# LKS_074DO_0406.net
KiCad netlist of a schematic drawn in Altium Designer
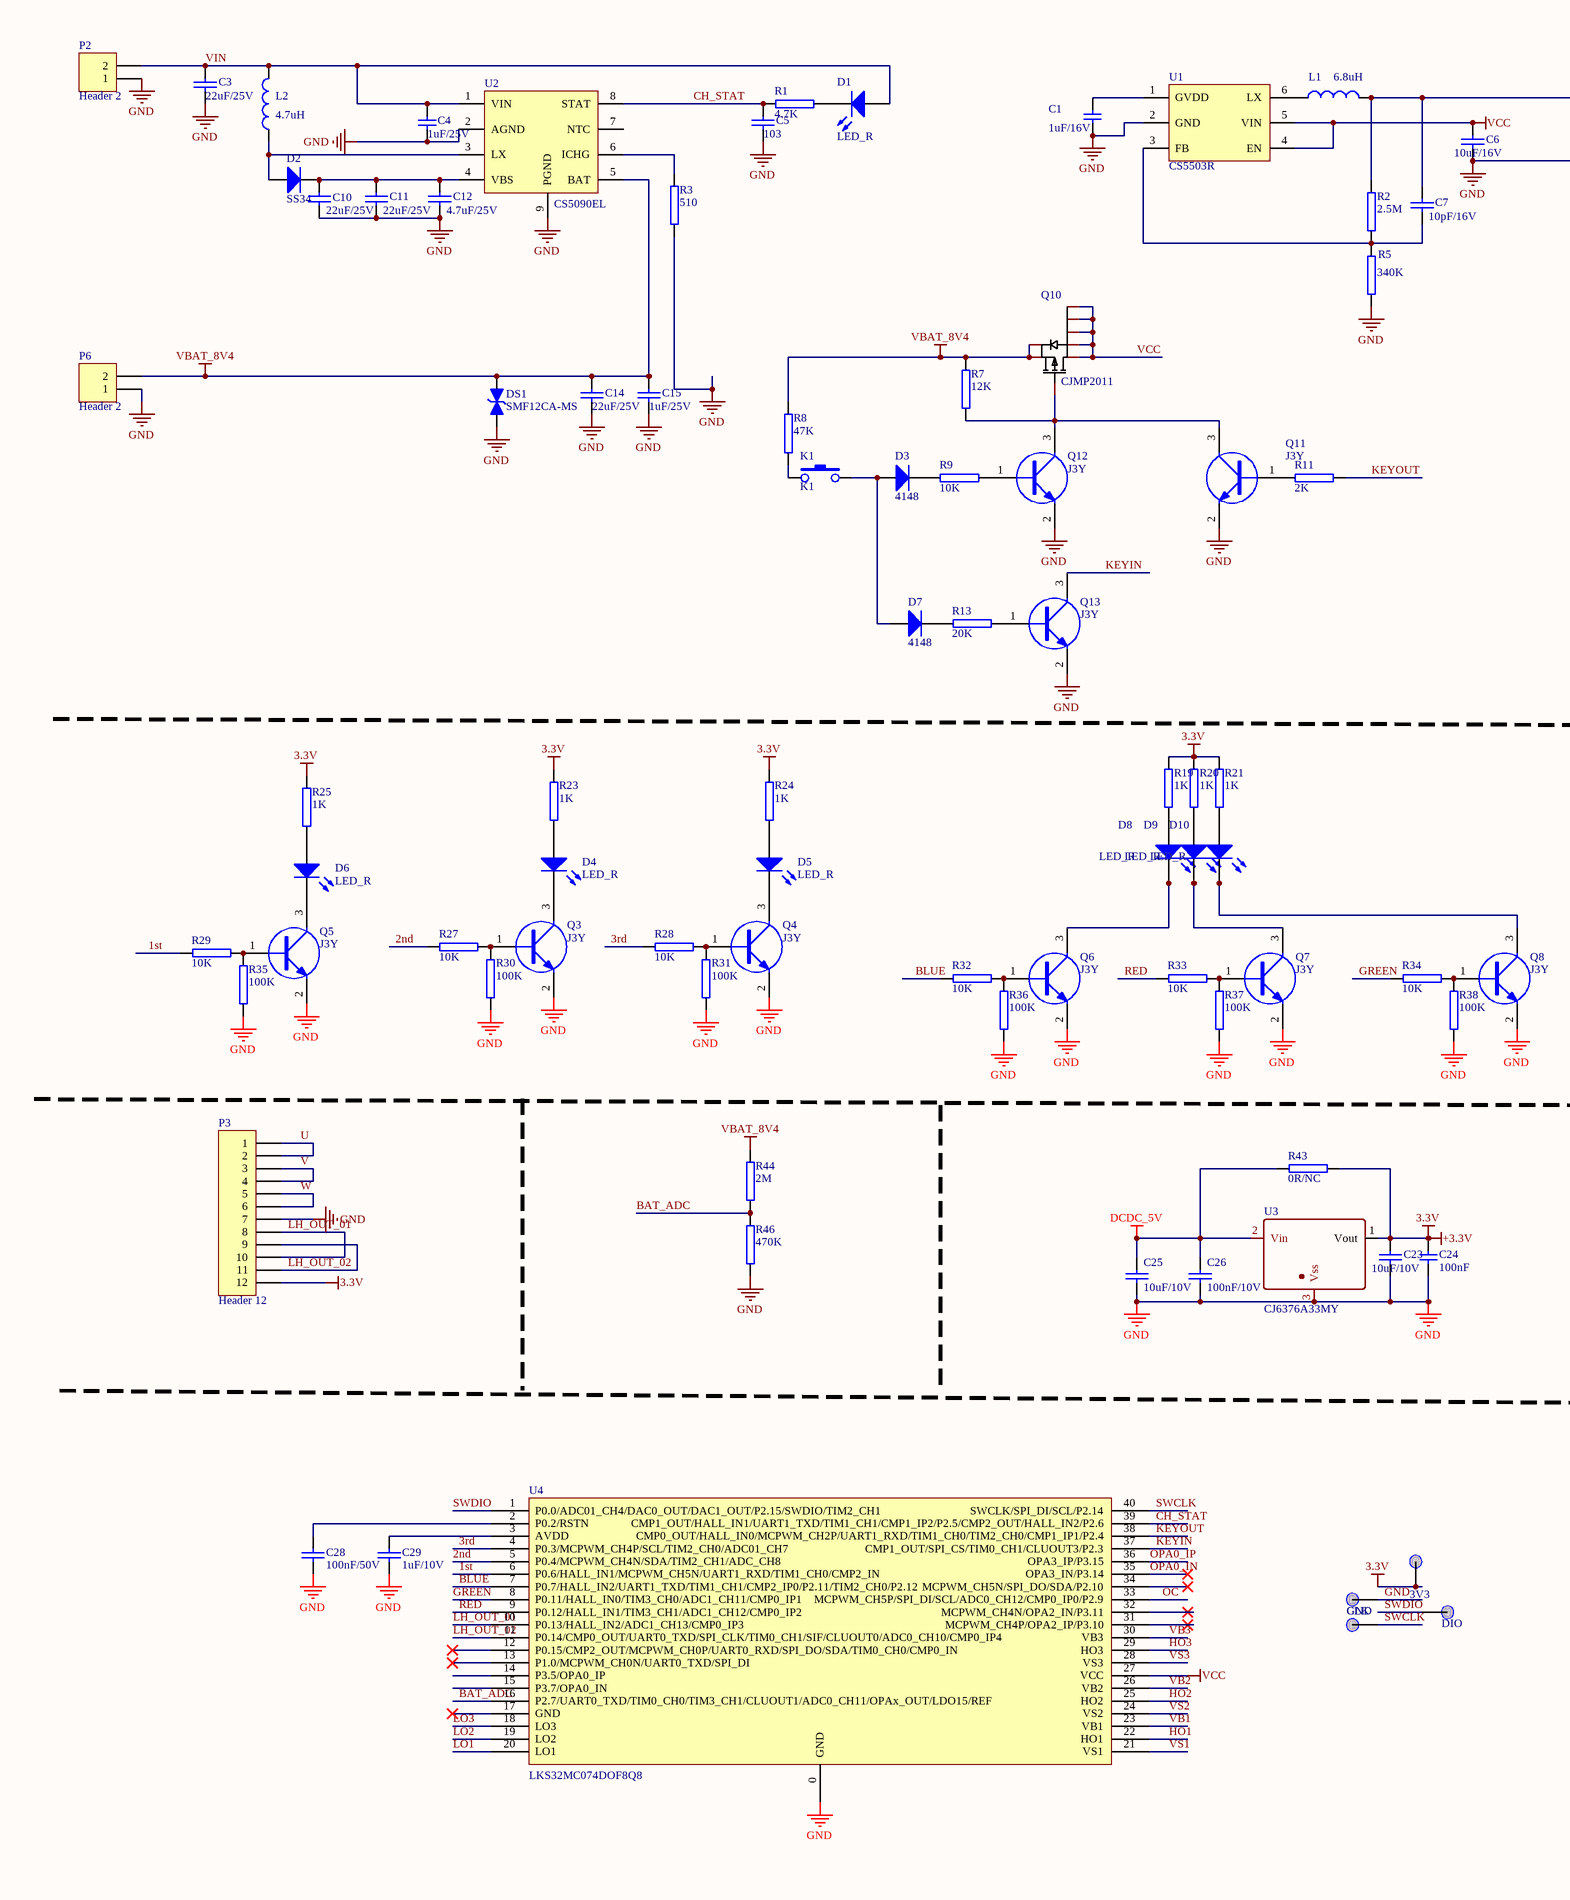
[diagram p0: LKS_074DO_0406.SchDoc, left]
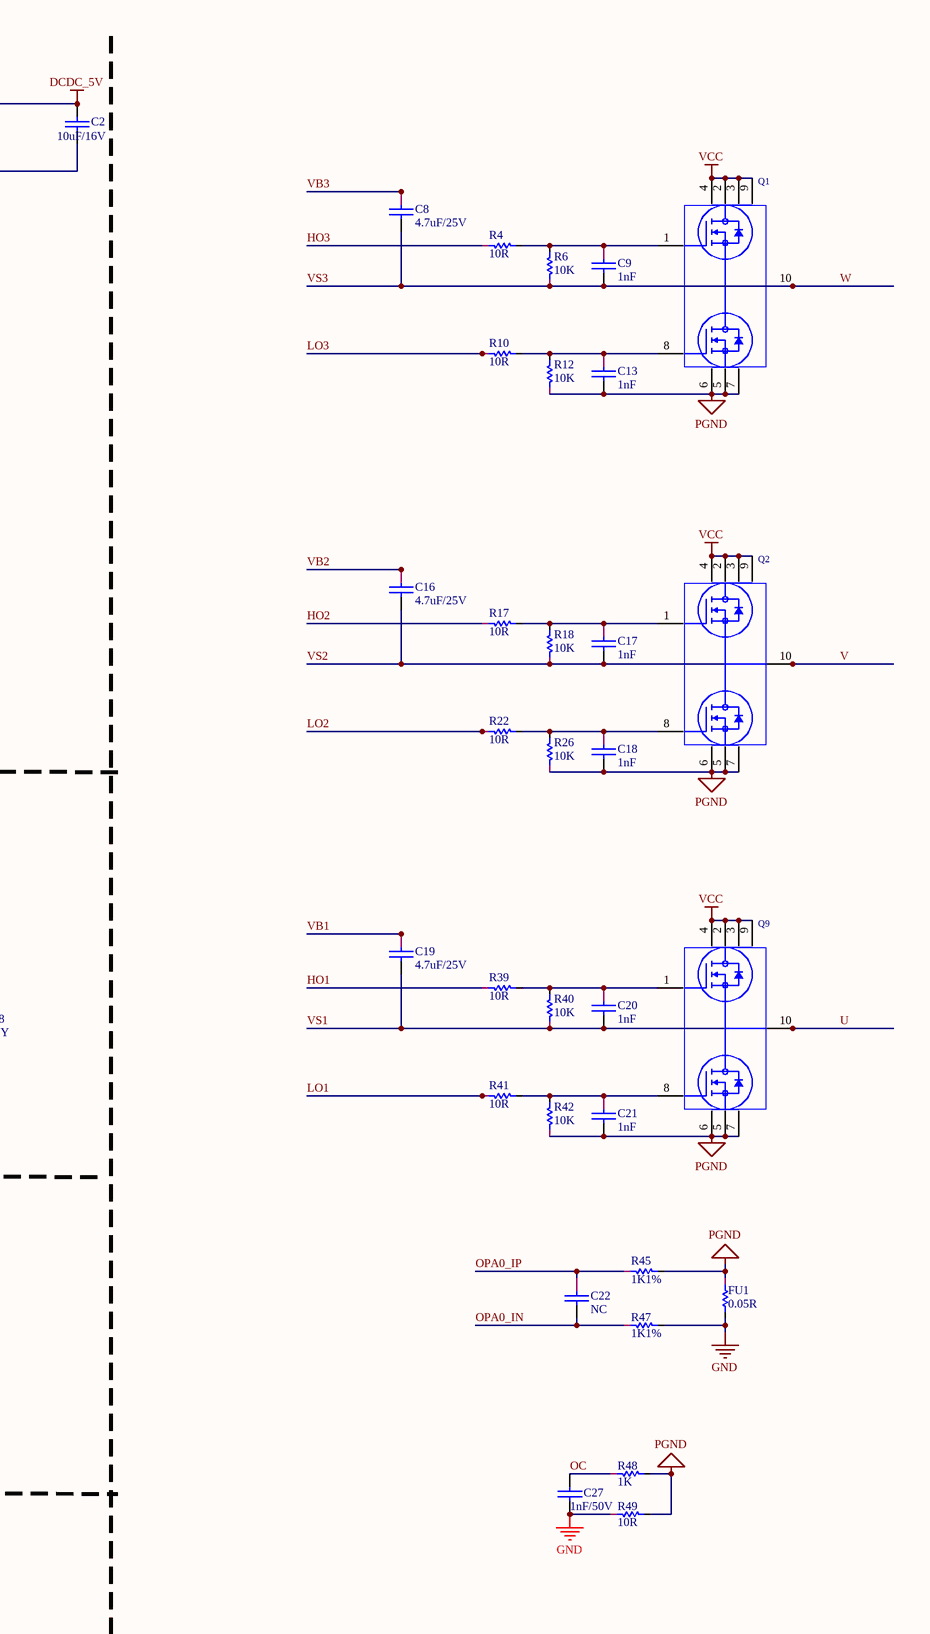
[diagram p1: LKS_074DO_0406.SchDoc, right]

(export (version "E")
  (design (tool "Eeschema 10.0.6"))
  (components
    (comp (ref "3V3") (value "test") (footprint "piot") (libsource (lib "LKS074DO_BRUSH_0329") (part "test")))
    (comp (ref "C1") (value "1uF/16V") (footprint "C 0402_M") (libsource (lib "") (part "CAP_2")))
    (comp (ref "C2")
      (value "10uF/16V")
      (footprint "C 0603_M")
      (description "Capacitor")
      (libsource (lib "") (part "CAP_1"))
    )
    (comp (ref "C3")
      (value "22uF/25V")
      (footprint "C 0603_M")
      (description "Capacitor")
      (libsource (lib "") (part "CAP_1"))
    )
    (comp (ref "C4") (value "1uF/25V") (footprint "C 0402_M") (libsource (lib "") (part "CAP_2")))
    (comp (ref "C5")
      (value "103")
      (footprint "R 0402_M")
      (description "Capacitor")
      (libsource (lib "") (part "CAP_1"))
    )
    (comp (ref "C6")
      (value "10uF/16V")
      (footprint "C 0603_M")
      (description "Capacitor")
      (libsource (lib "") (part "CAP_1"))
    )
    (comp (ref "C7")
      (value "10pF/16V")
      (footprint "C 0402_M")
      (description "Capacitor")
      (libsource (lib "") (part "CAP_1"))
    )
    (comp (ref "C8")
      (value "4.7uF/25V")
      (footprint "C 0402_M")
      (description "Capacitor")
      (libsource (lib "*") (part "CAP"))
    )
    (comp (ref "C9")
      (value "1nF")
      (footprint "C 0402_M")
      (description "Capacitor")
      (libsource (lib "*") (part "CAP"))
    )
    (comp (ref "C10")
      (value "22uF/25V")
      (footprint "C 0603_M")
      (description "Capacitor")
      (libsource (lib "") (part "CAP_1"))
    )
    (comp (ref "C11")
      (value "22uF/25V")
      (footprint "C 0603_M")
      (description "Capacitor")
      (libsource (lib "") (part "CAP_1"))
    )
    (comp (ref "C12")
      (value "4.7uF/25V")
      (footprint "C 0402_M")
      (description "Capacitor")
      (libsource (lib "") (part "CAP_1"))
    )
    (comp (ref "C13")
      (value "1nF")
      (footprint "C 0402_M")
      (description "Capacitor")
      (libsource (lib "*") (part "CAP"))
    )
    (comp (ref "C14")
      (value "22uF/25V")
      (footprint "C 0603_M")
      (description "Capacitor")
      (libsource (lib "") (part "CAP_1"))
    )
    (comp (ref "C15")
      (value "1uF/25V")
      (footprint "C 0402_M")
      (description "Capacitor")
      (libsource (lib "") (part "CAP_1"))
    )
    (comp (ref "C16")
      (value "4.7uF/25V")
      (footprint "C 0402_M")
      (description "Capacitor")
      (libsource (lib "*") (part "CAP"))
    )
    (comp (ref "C17")
      (value "1nF")
      (footprint "C 0402_M")
      (description "Capacitor")
      (libsource (lib "*") (part "CAP"))
    )
    (comp (ref "C18")
      (value "1nF")
      (footprint "C 0402_M")
      (description "Capacitor")
      (libsource (lib "*") (part "CAP"))
    )
    (comp (ref "C19")
      (value "4.7uF/25V")
      (footprint "C 0402_M")
      (description "Capacitor")
      (libsource (lib "*") (part "CAP"))
    )
    (comp (ref "C20")
      (value "1nF")
      (footprint "C 0402_M")
      (description "Capacitor")
      (libsource (lib "*") (part "CAP"))
    )
    (comp (ref "C21")
      (value "1nF")
      (footprint "C 0402_M")
      (description "Capacitor")
      (libsource (lib "*") (part "CAP"))
    )
    (comp (ref "C22")
      (value "NC")
      (footprint "C 0402_M")
      (description "Capacitor")
      (libsource (lib "*") (part "CAP"))
    )
    (comp (ref "C23")
      (value "10uF/10V")
      (footprint "C 0603_M")
      (description "Capacitor")
      (libsource (lib "") (part "CAP_1"))
    )
    (comp (ref "C24") (value "100nF") (footprint "C 0402_M") (libsource (lib "") (part "CAP_2")))
    (comp (ref "C25")
      (value "10uF/10V")
      (footprint "C 0603_M")
      (description "Capacitor")
      (libsource (lib "") (part "CAP_1"))
    )
    (comp (ref "C26")
      (value "100nF/10V")
      (footprint "C 0402_M")
      (description "Capacitor")
      (libsource (lib "") (part "CAP_1"))
    )
    (comp (ref "C27")
      (value "1nF/50V")
      (footprint "C 0402_M")
      (description "Capacitor")
      (libsource (lib "*") (part "C"))
    )
    (comp (ref "C28")
      (value "100nF/50V")
      (footprint "C 0402_M")
      (description "Capacitor")
      (libsource (lib "*") (part "C"))
    )
    (comp (ref "C29")
      (value "1uF/10V")
      (footprint "C 0402_M")
      (description "Capacitor")
      (libsource (lib "*") (part "C"))
    )
    (comp (ref "CLK") (value "test") (footprint "piot") (libsource (lib "LKS074DO_BRUSH_0329") (part "test")))
    (comp (ref "D1") (value "LED_R") (footprint "0603-LED") (libsource (lib "PuXun1") (part "LED")))
    (comp (ref "D2")
      (value "SS34")
      (footprint "SOD123FL")
      (description "Default Diode")
      (fields (field (name "PUBLISHER") "Altium Limited"))
      (libsource (lib "LKS034DO_Motor_0520_1") (part "Diode"))
    )
    (comp (ref "D3")
      (value "4148")
      (footprint "SOD-323")
      (description "Default Diode")
      (fields (field (name "PUBLISHER") "Altium Limited"))
      (libsource (lib "LKS034DO_Motor_0520_1") (part "Diode"))
    )
    (comp (ref "D4") (value "LED_R") (footprint "0603-LED") (libsource (lib "PuXun1") (part "LED")))
    (comp (ref "D5") (value "LED_R") (footprint "0603-LED") (libsource (lib "PuXun1") (part "LED")))
    (comp (ref "D6") (value "LED_R") (footprint "0603-LED") (libsource (lib "PuXun1") (part "LED")))
    (comp (ref "D7")
      (value "4148")
      (footprint "SOD-323")
      (description "Default Diode")
      (fields (field (name "PUBLISHER") "Altium Limited"))
      (libsource (lib "LKS034DO_Motor_0520_1") (part "Diode"))
    )
    (comp (ref "D8") (value "LED_R") (footprint "0603-LED") (libsource (lib "PuXun1") (part "LED")))
    (comp (ref "D9") (value "LED_R") (footprint "0603-LED") (libsource (lib "PuXun1") (part "LED")))
    (comp (ref "D10") (value "LED_R") (footprint "0603-LED") (libsource (lib "PuXun1") (part "LED")))
    (comp (ref "DIO") (value "test") (footprint "piot") (libsource (lib "LKS074DO_BRUSH_0329") (part "test")))
    (comp (ref "DS1")
      (value "SMF12CA-MS")
      (footprint "SOD-123F")
      (description "12V/19.9V")
      (libsource (lib "*") (part "DIODE-3"))
    )
    (comp (ref "FU1") (value "0.05R") (footprint "R 0805_M") (libsource (lib "*") (part "RAS")))
    (comp (ref "GND") (value "test") (footprint "piot") (libsource (lib "LKS074DO_BRUSH_0329") (part "test")))
    (comp (ref "K1") (value "K1") (footprint "SMD3.3X3.3X2") (libsource (lib "SCHLIB_NEW") (part "K1")))
    (comp (ref "L1")
      (value "6.8uH")
      (footprint "SMD3.5X3 .2- duplicate")
      (description "Inductor")
      (fields (field (name "PUBLISHER") "Altium Limited"))
      (libsource (lib "Miscellaneous Devices") (part "Inductor"))
    )
    (comp (ref "L2")
      (value "4.7uH")
      (footprint "SMD3.5X3 .2- duplicate")
      (description "Inductor")
      (fields (field (name "PUBLISHER") "Altium Limited"))
      (libsource (lib "Miscellaneous Devices") (part "Inductor"))
    )
    (comp (ref "P2")
      (value "Header 2")
      (footprint "CONN_SMD_2P_0.6")
      (description "Header, 2-Pin")
      (fields (field (name "PUBLISHER") "Altium Limited"))
      (libsource (lib "Miscellaneous Connectors") (part "Header 2"))
    )
    (comp (ref "P3")
      (value "Header 12")
      (footprint "SMD-12")
      (description "Header, 12-Pin")
      (fields (field (name "PUBLISHER") "Altium Limited"))
      (libsource (lib "Miscellaneous Connectors") (part "Header 12"))
    )
    (comp (ref "P6")
      (value "Header 2")
      (footprint "CONN_SMD_2P_0.6")
      (description "Header, 2-Pin")
      (fields (field (name "PUBLISHER") "Altium Limited"))
      (libsource (lib "Miscellaneous Connectors") (part "Header 2"))
    )
    (comp (ref "Q1") (value "CJBM3020") (footprint "DFN-3X3_8") (libsource (lib "*") (part "CJBM3020")))
    (comp (ref "Q2") (value "CJBM3020") (footprint "DFN-3X3_8") (libsource (lib "*") (part "CJBM3020")))
    (comp (ref "Q3")
      (value "J3Y")
      (footprint "SOT-23")
      (description "NPN Transistor")
      (libsource (lib "*") (part "NPN"))
    )
    (comp (ref "Q4")
      (value "J3Y")
      (footprint "SOT-23")
      (description "NPN Transistor")
      (libsource (lib "*") (part "NPN"))
    )
    (comp (ref "Q5")
      (value "J3Y")
      (footprint "SOT-23")
      (description "NPN Transistor")
      (libsource (lib "*") (part "NPN"))
    )
    (comp (ref "Q6")
      (value "J3Y")
      (footprint "SOT-23")
      (description "NPN Transistor")
      (libsource (lib "*") (part "NPN"))
    )
    (comp (ref "Q7")
      (value "J3Y")
      (footprint "SOT-23")
      (description "NPN Transistor")
      (libsource (lib "*") (part "NPN"))
    )
    (comp (ref "Q8")
      (value "J3Y")
      (footprint "SOT-23")
      (description "NPN Transistor")
      (libsource (lib "*") (part "NPN"))
    )
    (comp (ref "Q9") (value "CJBM3020") (footprint "DFN-3X3_8") (libsource (lib "*") (part "CJBM3020")))
    (comp (ref "Q10")
      (value "CJMP2011")
      (footprint "DFN-6-2X2")
      (libsource (lib "LKS074DO_BRUSH_0329") (part "CJMP2011"))
    )
    (comp (ref "Q11")
      (value "J3Y")
      (footprint "SOT-23")
      (description "NPN Transistor")
      (libsource (lib "*") (part "NPN"))
    )
    (comp (ref "Q12")
      (value "J3Y")
      (footprint "SOT-23")
      (description "NPN Transistor")
      (libsource (lib "*") (part "NPN"))
    )
    (comp (ref "Q13")
      (value "J3Y")
      (footprint "SOT-23")
      (description "NPN Transistor")
      (libsource (lib "*") (part "NPN"))
    )
    (comp (ref "R1") (value "4.7K") (footprint "C 0402_M") (libsource (lib "*") (part "RES2_S")))
    (comp (ref "R2") (value "2.5M") (footprint "C 0402_M") (libsource (lib "*") (part "RES2_S")))
    (comp (ref "R3") (value "510") (footprint "R 0402_M") (libsource (lib "*") (part "RES2_S")))
    (comp (ref "R4") (value "10R") (footprint "R 0402_M") (libsource (lib "*") (part "RAS")))
    (comp (ref "R5") (value "340K") (footprint "C 0402_M") (libsource (lib "*") (part "RES2_S")))
    (comp (ref "R6") (value "10K") (footprint "R 0402_M") (libsource (lib "*") (part "RAS")))
    (comp (ref "R7") (value "12K") (footprint "C 0402_M") (libsource (lib "*") (part "RES2_S")))
    (comp (ref "R8") (value "47K") (footprint "C 0402_M") (libsource (lib "*") (part "RES2_S")))
    (comp (ref "R9") (value "10K") (footprint "C 0402_M") (libsource (lib "*") (part "RES2_S")))
    (comp (ref "R10") (value "10R") (footprint "R 0402_M") (libsource (lib "*") (part "RAS")))
    (comp (ref "R11") (value "2K") (footprint "C 0402_M") (libsource (lib "*") (part "RES2_S")))
    (comp (ref "R12") (value "10K") (footprint "R 0402_M") (libsource (lib "*") (part "RAS")))
    (comp (ref "R13") (value "20K") (footprint "C 0402_M") (libsource (lib "*") (part "RES2_S")))
    (comp (ref "R17") (value "10R") (footprint "R 0402_M") (libsource (lib "*") (part "RAS")))
    (comp (ref "R18") (value "10K") (footprint "R 0402_M") (libsource (lib "*") (part "RAS")))
    (comp (ref "R19") (value "1K") (footprint "C 0402_M") (libsource (lib "*") (part "RES2_S")))
    (comp (ref "R20") (value "1K") (footprint "C 0402_M") (libsource (lib "*") (part "RES2_S")))
    (comp (ref "R21") (value "1K") (footprint "C 0402_M") (libsource (lib "*") (part "RES2_S")))
    (comp (ref "R22") (value "10R") (footprint "R 0402_M") (libsource (lib "*") (part "RAS")))
    (comp (ref "R23") (value "1K") (footprint "C 0402_M") (libsource (lib "*") (part "RES2_S")))
    (comp (ref "R24") (value "1K") (footprint "C 0402_M") (libsource (lib "*") (part "RES2_S")))
    (comp (ref "R25") (value "1K") (footprint "C 0402_M") (libsource (lib "*") (part "RES2_S")))
    (comp (ref "R26") (value "10K") (footprint "R 0402_M") (libsource (lib "*") (part "RAS")))
    (comp (ref "R27") (value "10K") (footprint "C 0402_M") (libsource (lib "*") (part "RES2_S")))
    (comp (ref "R28") (value "10K") (footprint "C 0402_M") (libsource (lib "*") (part "RES2_S")))
    (comp (ref "R29") (value "10K") (footprint "C 0402_M") (libsource (lib "*") (part "RES2_S")))
    (comp (ref "R30") (value "100K") (footprint "C 0402_M") (libsource (lib "*") (part "RES2_S")))
    (comp (ref "R31") (value "100K") (footprint "C 0402_M") (libsource (lib "*") (part "RES2_S")))
    (comp (ref "R32") (value "10K") (footprint "C 0402_M") (libsource (lib "*") (part "RES2_S")))
    (comp (ref "R33") (value "10K") (footprint "C 0402_M") (libsource (lib "*") (part "RES2_S")))
    (comp (ref "R34") (value "10K") (footprint "C 0402_M") (libsource (lib "*") (part "RES2_S")))
    (comp (ref "R35") (value "100K") (footprint "C 0402_M") (libsource (lib "*") (part "RES2_S")))
    (comp (ref "R36") (value "100K") (footprint "C 0402_M") (libsource (lib "*") (part "RES2_S")))
    (comp (ref "R37") (value "100K") (footprint "C 0402_M") (libsource (lib "*") (part "RES2_S")))
    (comp (ref "R38") (value "100K") (footprint "C 0402_M") (libsource (lib "*") (part "RES2_S")))
    (comp (ref "R39") (value "10R") (footprint "R 0402_M") (libsource (lib "*") (part "RAS")))
    (comp (ref "R40") (value "10K") (footprint "R 0402_M") (libsource (lib "*") (part "RAS")))
    (comp (ref "R41") (value "10R") (footprint "R 0402_M") (libsource (lib "*") (part "RAS")))
    (comp (ref "R42") (value "10K") (footprint "R 0402_M") (libsource (lib "*") (part "RAS")))
    (comp (ref "R43") (value "0R/NC") (footprint "0603") (libsource (lib "*") (part "RES2_S")))
    (comp (ref "R44") (value "2M") (footprint "C 0402_M") (libsource (lib "*") (part "RES2_S")))
    (comp (ref "R45") (value "1K1%") (footprint "R 0402_M") (libsource (lib "*") (part "RAS")))
    (comp (ref "R46") (value "470K") (footprint "C 0402_M") (libsource (lib "*") (part "RES2_S")))
    (comp (ref "R47") (value "1K1%") (footprint "R 0402_M") (libsource (lib "*") (part "RAS")))
    (comp (ref "R48") (value "1K") (footprint "R 0402_M") (libsource (lib "*") (part "RAS")))
    (comp (ref "R49") (value "10R") (footprint "R 0402_M") (libsource (lib "*") (part "RAS")))
    (comp (ref "U1")
      (value "CS5503R")
      (footprint "SOT23-6L")
      (libsource (lib "LKS034DO_Motor_0520_1") (part "CS5503R"))
    )
    (comp (ref "U2")
      (value "CS5090EL")
      (footprint "DFN2X2_8_0.5")
      (libsource (lib "LKS034DO_Motor_0520_1") (part "CS5090EL"))
    )
    (comp (ref "U3")
      (value "CJ6376A33MY")
      (footprint "SOT-23")
      (libsource (lib "LKS034DO_Motor_0520_1") (part "78L15"))
    )
    (comp (ref "U4")
      (value "LKS32MC074DOF8Q8")
      (footprint "QFN40")
      (description "芯片")
      (libsource (lib "Q_LINKO_V1.0") (part "LKS32MC074DF8Q8"))
    )
  )
  (nets
    (net (code "1") (name "+3.3V") (class "Default")
      (node (ref "3V3") (pin "1") (pinfunction "1_1") (pintype "passive"))
      (node (ref "C23") (pin "2") (pinfunction "2_2") (pintype "passive"))
      (node (ref "C24") (pin "1") (pinfunction "1_1") (pintype "passive"))
      (node (ref "P3") (pin "12") (pinfunction "12_12") (pintype "passive"))
      (node (ref "R19") (pin "2") (pinfunction "2_2") (pintype "passive"))
      (node (ref "R20") (pin "2") (pinfunction "2_2") (pintype "passive"))
      (node (ref "R21") (pin "2") (pinfunction "2_2") (pintype "passive"))
      (node (ref "R23") (pin "2") (pinfunction "2_2") (pintype "passive"))
      (node (ref "R24") (pin "2") (pinfunction "2_2") (pintype "passive"))
      (node (ref "R25") (pin "2") (pinfunction "2_2") (pintype "passive"))
      (node (ref "R43") (pin "2") (pinfunction "2_2") (pintype "passive"))
      (node (ref "U3") (pin "1") (pinfunction "Vout_1") (pintype "passive"))
    )
    (net (code "2") (name "/1st") (class "Default")
      (node (ref "R29") (pin "2") (pinfunction "2_2") (pintype "passive"))
      (node (ref "U4") (pin "6") (pinfunction "P0.6/HALL_IN1/MCPWM_CH5N/UART1_RXD/TIM1_CH0/CMP2_IN_6") (pintype "passive"))
    )
    (net (code "3") (name "/2nd") (class "Default")
      (node (ref "R27") (pin "2") (pinfunction "2_2") (pintype "passive"))
      (node (ref "U4") (pin "5") (pinfunction "P0.4/MCPWM_CH4N/SDA/TIM2_CH1/ADC_CH8_5") (pintype "passive"))
    )
    (net (code "4") (name "/3rd") (class "Default")
      (node (ref "R28") (pin "2") (pinfunction "2_2") (pintype "passive"))
      (node (ref "U4") (pin "4") (pinfunction "P0.3/MCPWM_CH4P/SCL/TIM2_CH0/ADC01_CH7_4") (pintype "passive"))
    )
    (net (code "5") (name "/BAT_ADC") (class "Default")
      (node (ref "R44") (pin "2") (pinfunction "2_2") (pintype "passive"))
      (node (ref "R46") (pin "1") (pinfunction "1_1") (pintype "passive"))
      (node (ref "U4") (pin "16") (pinfunction "P2.7/UART0_TXD/TIM0_CH0/TIM3_CH1/CLUOUT1/ADC0_CH11/OPAx_OUT/LDO15/REF_16") (pintype "passive"))
    )
    (net (code "6") (name "/BLUE") (class "Default")
      (node (ref "R32") (pin "2") (pinfunction "2_2") (pintype "passive"))
      (node (ref "U4") (pin "7") (pinfunction "P0.7/HALL_IN2/UART1_TXD/TIM1_CH1/CMP2_IP0/P2.11/TIM2_CH0/P2.12_7") (pintype "passive"))
    )
    (net (code "7") (name "/CH_STAT") (class "Default")
      (node (ref "C5") (pin "2") (pinfunction "2_2") (pintype "passive"))
      (node (ref "R1") (pin "1") (pinfunction "1_1") (pintype "passive"))
      (node (ref "U2") (pin "8") (pinfunction "STAT_8") (pintype "passive"))
      (node (ref "U4") (pin "39") (pinfunction "CMP1_OUT/HALL_IN1/UART1_TXD/TIM1_CH1/CMP1_IP2/P2.5/CMP2_OUT/HALL_IN2/P2.6_39") (pintype "passive"))
    )
    (net (code "8") (name "/GREEN") (class "Default")
      (node (ref "R34") (pin "2") (pinfunction "2_2") (pintype "passive"))
      (node (ref "U4") (pin "8") (pinfunction "P0.11/HALL_IN0/TIM3_CH0/ADC1_CH11/CMP0_IP1_8") (pintype "passive"))
    )
    (net (code "9") (name "/HO1") (class "Default")
      (node (ref "R39") (pin "2") (pinfunction "2_2") (pintype "passive"))
      (node (ref "U4") (pin "22") (pinfunction "HO1_22") (pintype "passive"))
    )
    (net (code "10") (name "/HO2") (class "Default")
      (node (ref "R17") (pin "2") (pinfunction "2_2") (pintype "passive"))
      (node (ref "U4") (pin "25") (pinfunction "HO2_25") (pintype "passive"))
    )
    (net (code "11") (name "/HO3") (class "Default")
      (node (ref "R4") (pin "2") (pinfunction "2_2") (pintype "passive"))
      (node (ref "U4") (pin "29") (pinfunction "HO3_29") (pintype "passive"))
    )
    (net (code "12") (name "/KEYIN") (class "Default")
      (node (ref "Q13") (pin "3") (pinfunction "C_3") (pintype "passive"))
      (node (ref "U4") (pin "37") (pinfunction "CMP1_OUT/SPI_CS/TIM0_CH1/CLUOUT3/P2.3_37") (pintype "passive"))
    )
    (net (code "13") (name "/KEYOUT") (class "Default")
      (node (ref "R11") (pin "2") (pinfunction "2_2") (pintype "passive"))
      (node (ref "U4") (pin "38") (pinfunction "CMP0_OUT/HALL_IN0/MCPWM_CH2P/UART1_RXD/TIM1_CH0/TIM2_CH0/CMP1_IP1/P2.4_38") (pintype "passive"))
    )
    (net (code "14") (name "/LH_OUT_01") (class "Default")
      (node (ref "P3") (pin "10") (pinfunction "10_10") (pintype "passive"))
      (node (ref "P3") (pin "8") (pinfunction "8_8") (pintype "passive"))
      (node (ref "U4") (pin "10") (pinfunction "P0.13/HALL_IN2/ADC1_CH13/CMP0_IP3_10") (pintype "passive"))
    )
    (net (code "15") (name "/LH_OUT_02") (class "Default")
      (node (ref "P3") (pin "11") (pinfunction "11_11") (pintype "passive"))
      (node (ref "P3") (pin "9") (pinfunction "9_9") (pintype "passive"))
      (node (ref "U4") (pin "11") (pinfunction "P0.14/CMP0_OUT/UART0_TXD/SPI_CLK/TIM0_CH1/SIF/CLUOUT0/ADC0_CH10/CMP0_IP4_11") (pintype "passive"))
    )
    (net (code "16") (name "/LO1") (class "Default")
      (node (ref "R41") (pin "2") (pinfunction "2_2") (pintype "passive"))
      (node (ref "U4") (pin "20") (pinfunction "LO1_20") (pintype "passive"))
    )
    (net (code "17") (name "/LO2") (class "Default")
      (node (ref "R22") (pin "2") (pinfunction "2_2") (pintype "passive"))
      (node (ref "U4") (pin "19") (pinfunction "LO2_19") (pintype "passive"))
    )
    (net (code "18") (name "/LO3") (class "Default")
      (node (ref "R10") (pin "2") (pinfunction "2_2") (pintype "passive"))
      (node (ref "U4") (pin "18") (pinfunction "LO3_18") (pintype "passive"))
    )
    (net (code "19") (name "/OC") (class "Default")
      (node (ref "C27") (pin "2") (pinfunction "2_2") (pintype "passive"))
      (node (ref "R48") (pin "2") (pinfunction "2_2") (pintype "passive"))
      (node (ref "U4") (pin "33") (pinfunction "MCPWM_CH5P/SPI_DI/SCL/ADC0_CH12/CMP0_IP0/P2.9_33") (pintype "passive"))
    )
    (net (code "20") (name "/OPA0_IN") (class "Default")
      (node (ref "C22") (pin "1") (pinfunction "1_1") (pintype "passive"))
      (node (ref "R47") (pin "2") (pinfunction "2_2") (pintype "passive"))
      (node (ref "U4") (pin "35") (pinfunction "OPA3_IN/P3.14_35") (pintype "passive"))
    )
    (net (code "21") (name "/OPA0_IP") (class "Default")
      (node (ref "C22") (pin "2") (pinfunction "2_2") (pintype "passive"))
      (node (ref "R45") (pin "2") (pinfunction "2_2") (pintype "passive"))
      (node (ref "U4") (pin "36") (pinfunction "OPA3_IP/P3.15_36") (pintype "passive"))
    )
    (net (code "22") (name "/RED") (class "Default")
      (node (ref "R33") (pin "2") (pinfunction "2_2") (pintype "passive"))
      (node (ref "U4") (pin "9") (pinfunction "P0.12/HALL_IN1/TIM3_CH1/ADC1_CH12/CMP0_IP2_9") (pintype "passive"))
    )
    (net (code "23") (name "/SWCLK") (class "Default")
      (node (ref "CLK") (pin "1") (pinfunction "1_1") (pintype "passive"))
      (node (ref "U4") (pin "40") (pinfunction "SWCLK/SPI_DI/SCL/P2.14_40") (pintype "passive"))
    )
    (net (code "24") (name "/SWDIO") (class "Default")
      (node (ref "DIO") (pin "1") (pinfunction "1_1") (pintype "passive"))
      (node (ref "U4") (pin "1") (pinfunction "P0.0/ADC01_CH4/DAC0_OUT/DAC1_OUT/P2.15/SWDIO/TIM2_CH1_1") (pintype "passive"))
    )
    (net (code "25") (name "/U") (class "Default")
      (node (ref "C19") (pin "1") (pinfunction "1_1") (pintype "passive"))
      (node (ref "C20") (pin "1") (pinfunction "1_1") (pintype "passive"))
      (node (ref "P3") (pin "1") (pinfunction "1_1") (pintype "passive"))
      (node (ref "P3") (pin "2") (pinfunction "2_2") (pintype "passive"))
      (node (ref "Q9") (pin "10") (pinfunction "S1/D2_10") (pintype "passive"))
      (node (ref "R40") (pin "2") (pinfunction "2_2") (pintype "passive"))
      (node (ref "U4") (pin "21") (pinfunction "VS1_21") (pintype "passive"))
    )
    (net (code "26") (name "/V") (class "Default")
      (node (ref "C16") (pin "1") (pinfunction "1_1") (pintype "passive"))
      (node (ref "C17") (pin "1") (pinfunction "1_1") (pintype "passive"))
      (node (ref "P3") (pin "3") (pinfunction "3_3") (pintype "passive"))
      (node (ref "P3") (pin "4") (pinfunction "4_4") (pintype "passive"))
      (node (ref "Q2") (pin "10") (pinfunction "S1/D2_10") (pintype "passive"))
      (node (ref "R18") (pin "2") (pinfunction "2_2") (pintype "passive"))
      (node (ref "U4") (pin "24") (pinfunction "VS2_24") (pintype "passive"))
    )
    (net (code "27") (name "/VB1") (class "Default")
      (node (ref "C19") (pin "2") (pinfunction "2_2") (pintype "passive"))
      (node (ref "U4") (pin "23") (pinfunction "VB1_23") (pintype "passive"))
    )
    (net (code "28") (name "/VB2") (class "Default")
      (node (ref "C16") (pin "2") (pinfunction "2_2") (pintype "passive"))
      (node (ref "U4") (pin "26") (pinfunction "VB2_26") (pintype "passive"))
    )
    (net (code "29") (name "/VB3") (class "Default")
      (node (ref "C8") (pin "2") (pinfunction "2_2") (pintype "passive"))
      (node (ref "U4") (pin "30") (pinfunction "VB3_30") (pintype "passive"))
    )
    (net (code "30") (name "/VIN") (class "Default")
      (node (ref "C3") (pin "2") (pinfunction "2_2") (pintype "passive"))
      (node (ref "C4") (pin "1") (pinfunction "1_1") (pintype "passive"))
      (node (ref "D1") (pin "1") (pinfunction "A_1") (pintype "passive"))
      (node (ref "L2") (pin "2") (pinfunction "2_2") (pintype "passive"))
      (node (ref "P2") (pin "2") (pinfunction "2_2") (pintype "passive"))
      (node (ref "U2") (pin "1") (pinfunction "VIN_1") (pintype "passive"))
    )
    (net (code "31") (name "/VS3") (class "Default")
      (node (ref "C8") (pin "1") (pinfunction "1_1") (pintype "passive"))
      (node (ref "C9") (pin "1") (pinfunction "1_1") (pintype "passive"))
      (node (ref "P3") (pin "5") (pinfunction "5_5") (pintype "passive"))
      (node (ref "P3") (pin "6") (pinfunction "6_6") (pintype "passive"))
      (node (ref "Q1") (pin "10") (pinfunction "S1/D2_10") (pintype "passive"))
      (node (ref "R6") (pin "2") (pinfunction "2_2") (pintype "passive"))
      (node (ref "U4") (pin "28") (pinfunction "VS3_28") (pintype "passive"))
    )
    (net (code "32") (name "DCDC_5V") (class "Default")
      (node (ref "C2") (pin "2") (pinfunction "2_2") (pintype "passive"))
      (node (ref "C25") (pin "2") (pinfunction "2_2") (pintype "passive"))
      (node (ref "C26") (pin "1") (pinfunction "1_1") (pintype "passive"))
      (node (ref "C7") (pin "2") (pinfunction "2_2") (pintype "passive"))
      (node (ref "L1") (pin "2") (pinfunction "2_2") (pintype "passive"))
      (node (ref "R2") (pin "1") (pinfunction "1_1") (pintype "passive"))
      (node (ref "R43") (pin "1") (pinfunction "1_1") (pintype "passive"))
      (node (ref "U3") (pin "2") (pinfunction "Vin_2") (pintype "passive"))
    )
    (net (code "33") (name "GND") (class "Default")
      (node (ref "C1") (pin "1") (pinfunction "1_1") (pintype "passive"))
      (node (ref "C10") (pin "1") (pinfunction "1_1") (pintype "passive"))
      (node (ref "C11") (pin "1") (pinfunction "1_1") (pintype "passive"))
      (node (ref "C12") (pin "1") (pinfunction "1_1") (pintype "passive"))
      (node (ref "C14") (pin "1") (pinfunction "1_1") (pintype "passive"))
      (node (ref "C15") (pin "1") (pinfunction "1_1") (pintype "passive"))
      (node (ref "C2") (pin "1") (pinfunction "1_1") (pintype "passive"))
      (node (ref "C23") (pin "1") (pinfunction "1_1") (pintype "passive"))
      (node (ref "C24") (pin "2") (pinfunction "2_2") (pintype "passive"))
      (node (ref "C25") (pin "1") (pinfunction "1_1") (pintype "passive"))
      (node (ref "C26") (pin "2") (pinfunction "2_2") (pintype "passive"))
      (node (ref "C27") (pin "1") (pinfunction "1_1") (pintype "passive"))
      (node (ref "C28") (pin "2") (pinfunction "2_2") (pintype "passive"))
      (node (ref "C29") (pin "1") (pinfunction "1_1") (pintype "passive"))
      (node (ref "C3") (pin "1") (pinfunction "1_1") (pintype "passive"))
      (node (ref "C4") (pin "2") (pinfunction "2_2") (pintype "passive"))
      (node (ref "C5") (pin "1") (pinfunction "1_1") (pintype "passive"))
      (node (ref "C6") (pin "1") (pinfunction "1_1") (pintype "passive"))
      (node (ref "DS1") (pin "2") (pinfunction "K_2") (pintype "passive"))
      (node (ref "FU1") (pin "1") (pinfunction "1_1") (pintype "passive"))
      (node (ref "GND") (pin "1") (pinfunction "1_1") (pintype "passive"))
      (node (ref "P2") (pin "1") (pinfunction "1_1") (pintype "passive"))
      (node (ref "P3") (pin "7") (pinfunction "7_7") (pintype "passive"))
      (node (ref "P6") (pin "1") (pinfunction "1_1") (pintype "passive"))
      (node (ref "Q11") (pin "2") (pinfunction "E_2") (pintype "passive"))
      (node (ref "Q12") (pin "2") (pinfunction "E_2") (pintype "passive"))
      (node (ref "Q13") (pin "2") (pinfunction "E_2") (pintype "passive"))
      (node (ref "Q3") (pin "2") (pinfunction "E_2") (pintype "passive"))
      (node (ref "Q4") (pin "2") (pinfunction "E_2") (pintype "passive"))
      (node (ref "Q5") (pin "2") (pinfunction "E_2") (pintype "passive"))
      (node (ref "Q6") (pin "2") (pinfunction "E_2") (pintype "passive"))
      (node (ref "Q7") (pin "2") (pinfunction "E_2") (pintype "passive"))
      (node (ref "Q8") (pin "2") (pinfunction "E_2") (pintype "passive"))
      (node (ref "R3") (pin "2") (pinfunction "2_2") (pintype "passive"))
      (node (ref "R30") (pin "2") (pinfunction "2_2") (pintype "passive"))
      (node (ref "R31") (pin "2") (pinfunction "2_2") (pintype "passive"))
      (node (ref "R35") (pin "2") (pinfunction "2_2") (pintype "passive"))
      (node (ref "R36") (pin "2") (pinfunction "2_2") (pintype "passive"))
      (node (ref "R37") (pin "2") (pinfunction "2_2") (pintype "passive"))
      (node (ref "R38") (pin "2") (pinfunction "2_2") (pintype "passive"))
      (node (ref "R46") (pin "2") (pinfunction "2_2") (pintype "passive"))
      (node (ref "R47") (pin "1") (pinfunction "1_1") (pintype "passive"))
      (node (ref "R49") (pin "2") (pinfunction "2_2") (pintype "passive"))
      (node (ref "R5") (pin "2") (pinfunction "2_2") (pintype "passive"))
      (node (ref "U1") (pin "2") (pinfunction "GND_2") (pintype "passive"))
      (node (ref "U2") (pin "2") (pinfunction "AGND_2") (pintype "passive"))
      (node (ref "U2") (pin "9") (pinfunction "PGND_9") (pintype "passive"))
      (node (ref "U3") (pin "3") (pinfunction "Vss_3") (pintype "passive"))
      (node (ref "U4") (pin "0") (pinfunction "GND_0") (pintype "passive"))
    )
    (net (code "34") (name "Net-(D1-K)") (class "Default")
      (node (ref "D1") (pin "2") (pinfunction "K_2") (pintype "passive"))
      (node (ref "R1") (pin "2") (pinfunction "2_2") (pintype "passive"))
    )
    (net (code "35") (name "Net-(D2-A)") (class "Default")
      (node (ref "D2") (pin "1") (pinfunction "A_1") (pintype "passive"))
      (node (ref "L2") (pin "1") (pinfunction "1_1") (pintype "passive"))
      (node (ref "U2") (pin "3") (pinfunction "LX_3") (pintype "passive"))
    )
    (net (code "36") (name "Net-(D2-K)") (class "Default")
      (node (ref "C10") (pin "2") (pinfunction "2_2") (pintype "passive"))
      (node (ref "C11") (pin "2") (pinfunction "2_2") (pintype "passive"))
      (node (ref "C12") (pin "2") (pinfunction "2_2") (pintype "passive"))
      (node (ref "D2") (pin "2") (pinfunction "K_2") (pintype "passive"))
      (node (ref "U2") (pin "4") (pinfunction "VBS_4") (pintype "passive"))
    )
    (net (code "37") (name "Net-(D3-A)") (class "Default")
      (node (ref "D3") (pin "1") (pinfunction "A_1") (pintype "passive"))
      (node (ref "D7") (pin "1") (pinfunction "A_1") (pintype "passive"))
      (node (ref "K1") (pin "2") (pintype "passive"))
    )
    (net (code "38") (name "Net-(D3-K)") (class "Default")
      (node (ref "D3") (pin "2") (pinfunction "K_2") (pintype "passive"))
      (node (ref "R9") (pin "1") (pinfunction "1_1") (pintype "passive"))
    )
    (net (code "39") (name "Net-(D4-A)") (class "Default")
      (node (ref "D4") (pin "1") (pinfunction "A_1") (pintype "passive"))
      (node (ref "R23") (pin "1") (pinfunction "1_1") (pintype "passive"))
    )
    (net (code "40") (name "Net-(D4-K)") (class "Default")
      (node (ref "D4") (pin "2") (pinfunction "K_2") (pintype "passive"))
      (node (ref "Q3") (pin "3") (pinfunction "C_3") (pintype "passive"))
    )
    (net (code "41") (name "Net-(D5-A)") (class "Default")
      (node (ref "D5") (pin "1") (pinfunction "A_1") (pintype "passive"))
      (node (ref "R24") (pin "1") (pinfunction "1_1") (pintype "passive"))
    )
    (net (code "42") (name "Net-(D5-K)") (class "Default")
      (node (ref "D5") (pin "2") (pinfunction "K_2") (pintype "passive"))
      (node (ref "Q4") (pin "3") (pinfunction "C_3") (pintype "passive"))
    )
    (net (code "43") (name "Net-(D6-A)") (class "Default")
      (node (ref "D6") (pin "1") (pinfunction "A_1") (pintype "passive"))
      (node (ref "R25") (pin "1") (pinfunction "1_1") (pintype "passive"))
    )
    (net (code "44") (name "Net-(D6-K)") (class "Default")
      (node (ref "D6") (pin "2") (pinfunction "K_2") (pintype "passive"))
      (node (ref "Q5") (pin "3") (pinfunction "C_3") (pintype "passive"))
    )
    (net (code "45") (name "Net-(D7-K)") (class "Default")
      (node (ref "D7") (pin "2") (pinfunction "K_2") (pintype "passive"))
      (node (ref "R13") (pin "1") (pinfunction "1_1") (pintype "passive"))
    )
    (net (code "46") (name "Net-(D8-A)") (class "Default")
      (node (ref "D8") (pin "1") (pinfunction "A_1") (pintype "passive"))
      (node (ref "R19") (pin "1") (pinfunction "1_1") (pintype "passive"))
    )
    (net (code "47") (name "Net-(D8-K)") (class "Default")
      (node (ref "D8") (pin "2") (pinfunction "K_2") (pintype "passive"))
      (node (ref "Q6") (pin "3") (pinfunction "C_3") (pintype "passive"))
    )
    (net (code "48") (name "Net-(D9-A)") (class "Default")
      (node (ref "D9") (pin "1") (pinfunction "A_1") (pintype "passive"))
      (node (ref "R20") (pin "1") (pinfunction "1_1") (pintype "passive"))
    )
    (net (code "49") (name "Net-(D9-K)") (class "Default")
      (node (ref "D9") (pin "2") (pinfunction "K_2") (pintype "passive"))
      (node (ref "Q7") (pin "3") (pinfunction "C_3") (pintype "passive"))
    )
    (net (code "50") (name "Net-(D10-A)") (class "Default")
      (node (ref "D10") (pin "1") (pinfunction "A_1") (pintype "passive"))
      (node (ref "R21") (pin "1") (pinfunction "1_1") (pintype "passive"))
    )
    (net (code "51") (name "Net-(D10-K)") (class "Default")
      (node (ref "D10") (pin "2") (pinfunction "K_2") (pintype "passive"))
      (node (ref "Q8") (pin "3") (pinfunction "C_3") (pintype "passive"))
    )
    (net (code "52") (name "Net-(K1-Pad1)") (class "Default")
      (node (ref "K1") (pin "1") (pintype "passive"))
      (node (ref "R8") (pin "1") (pinfunction "1_1") (pintype "passive"))
    )
    (net (code "53") (name "Net-(Q1-G1)") (class "Default")
      (node (ref "C9") (pin "2") (pinfunction "2_2") (pintype "passive"))
      (node (ref "Q1") (pin "1") (pinfunction "G1_1") (pintype "passive"))
      (node (ref "R4") (pin "1") (pinfunction "1_1") (pintype "passive"))
      (node (ref "R6") (pin "1") (pinfunction "1_1") (pintype "passive"))
    )
    (net (code "54") (name "Net-(Q1-G2)") (class "Default")
      (node (ref "C13") (pin "2") (pinfunction "2_2") (pintype "passive"))
      (node (ref "Q1") (pin "8") (pinfunction "G2_8") (pintype "passive"))
      (node (ref "R10") (pin "1") (pinfunction "1_1") (pintype "passive"))
      (node (ref "R12") (pin "1") (pinfunction "1_1") (pintype "passive"))
    )
    (net (code "55") (name "Net-(Q2-G1)") (class "Default")
      (node (ref "C17") (pin "2") (pinfunction "2_2") (pintype "passive"))
      (node (ref "Q2") (pin "1") (pinfunction "G1_1") (pintype "passive"))
      (node (ref "R17") (pin "1") (pinfunction "1_1") (pintype "passive"))
      (node (ref "R18") (pin "1") (pinfunction "1_1") (pintype "passive"))
    )
    (net (code "56") (name "Net-(Q2-G2)") (class "Default")
      (node (ref "C18") (pin "2") (pinfunction "2_2") (pintype "passive"))
      (node (ref "Q2") (pin "8") (pinfunction "G2_8") (pintype "passive"))
      (node (ref "R22") (pin "1") (pinfunction "1_1") (pintype "passive"))
      (node (ref "R26") (pin "1") (pinfunction "1_1") (pintype "passive"))
    )
    (net (code "57") (name "Net-(Q3-B)") (class "Default")
      (node (ref "Q3") (pin "1") (pinfunction "B_1") (pintype "passive"))
      (node (ref "R27") (pin "1") (pinfunction "1_1") (pintype "passive"))
      (node (ref "R30") (pin "1") (pinfunction "1_1") (pintype "passive"))
    )
    (net (code "58") (name "Net-(Q4-B)") (class "Default")
      (node (ref "Q4") (pin "1") (pinfunction "B_1") (pintype "passive"))
      (node (ref "R28") (pin "1") (pinfunction "1_1") (pintype "passive"))
      (node (ref "R31") (pin "1") (pinfunction "1_1") (pintype "passive"))
    )
    (net (code "59") (name "Net-(Q5-B)") (class "Default")
      (node (ref "Q5") (pin "1") (pinfunction "B_1") (pintype "passive"))
      (node (ref "R29") (pin "1") (pinfunction "1_1") (pintype "passive"))
      (node (ref "R35") (pin "1") (pinfunction "1_1") (pintype "passive"))
    )
    (net (code "60") (name "Net-(Q6-B)") (class "Default")
      (node (ref "Q6") (pin "1") (pinfunction "B_1") (pintype "passive"))
      (node (ref "R32") (pin "1") (pinfunction "1_1") (pintype "passive"))
      (node (ref "R36") (pin "1") (pinfunction "1_1") (pintype "passive"))
    )
    (net (code "61") (name "Net-(Q7-B)") (class "Default")
      (node (ref "Q7") (pin "1") (pinfunction "B_1") (pintype "passive"))
      (node (ref "R33") (pin "1") (pinfunction "1_1") (pintype "passive"))
      (node (ref "R37") (pin "1") (pinfunction "1_1") (pintype "passive"))
    )
    (net (code "62") (name "Net-(Q8-B)") (class "Default")
      (node (ref "Q8") (pin "1") (pinfunction "B_1") (pintype "passive"))
      (node (ref "R34") (pin "1") (pinfunction "1_1") (pintype "passive"))
      (node (ref "R38") (pin "1") (pinfunction "1_1") (pintype "passive"))
    )
    (net (code "63") (name "Net-(Q9-G1)") (class "Default")
      (node (ref "C20") (pin "2") (pinfunction "2_2") (pintype "passive"))
      (node (ref "Q9") (pin "1") (pinfunction "G1_1") (pintype "passive"))
      (node (ref "R39") (pin "1") (pinfunction "1_1") (pintype "passive"))
      (node (ref "R40") (pin "1") (pinfunction "1_1") (pintype "passive"))
    )
    (net (code "64") (name "Net-(Q9-G2)") (class "Default")
      (node (ref "C21") (pin "2") (pinfunction "2_2") (pintype "passive"))
      (node (ref "Q9") (pin "8") (pinfunction "G2_8") (pintype "passive"))
      (node (ref "R41") (pin "1") (pinfunction "1_1") (pintype "passive"))
      (node (ref "R42") (pin "1") (pinfunction "1_1") (pintype "passive"))
    )
    (net (code "65") (name "Net-(Q10-G)") (class "Default")
      (node (ref "Q10") (pin "3") (pinfunction "G_3") (pintype "passive"))
      (node (ref "Q11") (pin "3") (pinfunction "C_3") (pintype "passive"))
      (node (ref "Q12") (pin "3") (pinfunction "C_3") (pintype "passive"))
      (node (ref "R7") (pin "1") (pinfunction "1_1") (pintype "passive"))
    )
    (net (code "66") (name "Net-(Q11-B)") (class "Default")
      (node (ref "Q11") (pin "1") (pinfunction "B_1") (pintype "passive"))
      (node (ref "R11") (pin "1") (pinfunction "1_1") (pintype "passive"))
    )
    (net (code "67") (name "Net-(Q12-B)") (class "Default")
      (node (ref "Q12") (pin "1") (pinfunction "B_1") (pintype "passive"))
      (node (ref "R9") (pin "2") (pinfunction "2_2") (pintype "passive"))
    )
    (net (code "68") (name "Net-(Q13-B)") (class "Default")
      (node (ref "Q13") (pin "1") (pinfunction "B_1") (pintype "passive"))
      (node (ref "R13") (pin "2") (pinfunction "2_2") (pintype "passive"))
    )
    (net (code "69") (name "Net-(U1-FB)") (class "Default")
      (node (ref "C7") (pin "1") (pinfunction "1_1") (pintype "passive"))
      (node (ref "R2") (pin "2") (pinfunction "2_2") (pintype "passive"))
      (node (ref "R5") (pin "1") (pinfunction "1_1") (pintype "passive"))
      (node (ref "U1") (pin "3") (pinfunction "FB_3") (pintype "passive"))
    )
    (net (code "70") (name "Net-(U1-GVDD)") (class "Default")
      (node (ref "C1") (pin "2") (pinfunction "2_2") (pintype "passive"))
      (node (ref "U1") (pin "1") (pinfunction "GVDD_1") (pintype "passive"))
    )
    (net (code "71") (name "Net-(U1-LX)") (class "Default")
      (node (ref "L1") (pin "1") (pinfunction "1_1") (pintype "passive"))
      (node (ref "U1") (pin "6") (pinfunction "LX_6") (pintype "passive"))
    )
    (net (code "72") (name "Net-(U2-ICHG)") (class "Default")
      (node (ref "R3") (pin "1") (pinfunction "1_1") (pintype "passive"))
      (node (ref "U2") (pin "6") (pinfunction "ICHG_6") (pintype "passive"))
    )
    (net (code "73") (name "Net-(U4-AVDD)") (class "Default")
      (node (ref "C29") (pin "2") (pinfunction "2_2") (pintype "passive"))
      (node (ref "U4") (pin "3") (pinfunction "AVDD_3") (pintype "passive"))
    )
    (net (code "74") (name "Net-(U4-P0.2{slash}RSTN)") (class "Default")
      (node (ref "C28") (pin "1") (pinfunction "1_1") (pintype "passive"))
      (node (ref "U4") (pin "2") (pinfunction "P0.2/RSTN_2") (pintype "passive"))
    )
    (net (code "75") (name "PGND") (class "Default")
      (node (ref "C13") (pin "1") (pinfunction "1_1") (pintype "passive"))
      (node (ref "C18") (pin "1") (pinfunction "1_1") (pintype "passive"))
      (node (ref "C21") (pin "1") (pinfunction "1_1") (pintype "passive"))
      (node (ref "FU1") (pin "2") (pinfunction "2_2") (pintype "passive"))
      (node (ref "Q1") (pin "5") (pinfunction "S2_5") (pintype "passive"))
      (node (ref "Q1") (pin "6") (pinfunction "S2_6") (pintype "passive"))
      (node (ref "Q1") (pin "7") (pinfunction "S2_7") (pintype "passive"))
      (node (ref "Q2") (pin "5") (pinfunction "S2_5") (pintype "passive"))
      (node (ref "Q2") (pin "6") (pinfunction "S2_6") (pintype "passive"))
      (node (ref "Q2") (pin "7") (pinfunction "S2_7") (pintype "passive"))
      (node (ref "Q9") (pin "5") (pinfunction "S2_5") (pintype "passive"))
      (node (ref "Q9") (pin "6") (pinfunction "S2_6") (pintype "passive"))
      (node (ref "Q9") (pin "7") (pinfunction "S2_7") (pintype "passive"))
      (node (ref "R12") (pin "2") (pinfunction "2_2") (pintype "passive"))
      (node (ref "R26") (pin "2") (pinfunction "2_2") (pintype "passive"))
      (node (ref "R42") (pin "2") (pinfunction "2_2") (pintype "passive"))
      (node (ref "R45") (pin "1") (pinfunction "1_1") (pintype "passive"))
      (node (ref "R48") (pin "1") (pinfunction "1_1") (pintype "passive"))
      (node (ref "R49") (pin "1") (pinfunction "1_1") (pintype "passive"))
    )
    (net (code "76") (name "VBAT_8V4") (class "Default")
      (node (ref "C14") (pin "2") (pinfunction "2_2") (pintype "passive"))
      (node (ref "C15") (pin "2") (pinfunction "2_2") (pintype "passive"))
      (node (ref "DS1") (pin "1") (pinfunction "A_1") (pintype "passive"))
      (node (ref "P6") (pin "2") (pinfunction "2_2") (pintype "passive"))
      (node (ref "Q10") (pin "4") (pinfunction "S_4") (pintype "passive"))
      (node (ref "Q10") (pin "8") (pinfunction "S_8") (pintype "passive"))
      (node (ref "R44") (pin "1") (pinfunction "1_1") (pintype "passive"))
      (node (ref "R7") (pin "2") (pinfunction "2_2") (pintype "passive"))
      (node (ref "R8") (pin "2") (pinfunction "2_2") (pintype "passive"))
      (node (ref "U2") (pin "5") (pinfunction "BAT_5") (pintype "passive"))
    )
    (net (code "77") (name "VCC") (class "Default")
      (node (ref "C6") (pin "2") (pinfunction "2_2") (pintype "passive"))
      (node (ref "Q1") (pin "2") (pinfunction "D1_2") (pintype "passive"))
      (node (ref "Q1") (pin "3") (pinfunction "D1_3") (pintype "passive"))
      (node (ref "Q1") (pin "4") (pinfunction "D1_4") (pintype "passive"))
      (node (ref "Q1") (pin "9") (pinfunction "D1_9") (pintype "passive"))
      (node (ref "Q10") (pin "1") (pinfunction "D_1") (pintype "passive"))
      (node (ref "Q10") (pin "2") (pinfunction "D_2") (pintype "passive"))
      (node (ref "Q10") (pin "5") (pinfunction "D_5") (pintype "passive"))
      (node (ref "Q10") (pin "6") (pinfunction "D_6") (pintype "passive"))
      (node (ref "Q10") (pin "7") (pinfunction "D_7") (pintype "passive"))
      (node (ref "Q2") (pin "2") (pinfunction "D1_2") (pintype "passive"))
      (node (ref "Q2") (pin "3") (pinfunction "D1_3") (pintype "passive"))
      (node (ref "Q2") (pin "4") (pinfunction "D1_4") (pintype "passive"))
      (node (ref "Q2") (pin "9") (pinfunction "D1_9") (pintype "passive"))
      (node (ref "Q9") (pin "2") (pinfunction "D1_2") (pintype "passive"))
      (node (ref "Q9") (pin "3") (pinfunction "D1_3") (pintype "passive"))
      (node (ref "Q9") (pin "4") (pinfunction "D1_4") (pintype "passive"))
      (node (ref "Q9") (pin "9") (pinfunction "D1_9") (pintype "passive"))
      (node (ref "U1") (pin "4") (pinfunction "EN_4") (pintype "passive"))
      (node (ref "U1") (pin "5") (pinfunction "VIN_5") (pintype "passive"))
      (node (ref "U4") (pin "27") (pinfunction "VCC_27") (pintype "passive"))
    )
    (net (code "78") (name "unconnected-(U2-NTC-Pad7)") (class "Default")
      (node (ref "U2") (pin "7") (pinfunction "NTC_7") (pintype "passive"))
    )
    (net (code "79") (name "unconnected-(U4-GND-Pad17)") (class "Default")
      (node (ref "U4") (pin "17") (pinfunction "GND_17") (pintype "passive+no_connect"))
    )
    (net (code "80") (name "unconnected-(U4-MCPWM_CH4N{slash}OPA2_IN{slash}P3.11-Pad32)") (class "Default")
      (node (ref "U4") (pin "32") (pinfunction "MCPWM_CH4N/OPA2_IN/P3.11_32") (pintype "passive"))
    )
    (net (code "81") (name "unconnected-(U4-MCPWM_CH4P{slash}OPA2_IP{slash}P3.10-Pad31)") (class "Default")
      (node (ref "U4") (pin "31") (pinfunction "MCPWM_CH4P/OPA2_IP/P3.10_31") (pintype "passive"))
    )
    (net (code "82") (name "unconnected-(U4-MCPWM_CH5N{slash}SPI_DO{slash}SDA{slash}P2.10-Pad34)") (class "Default")
      (node (ref "U4") (pin "34") (pinfunction "MCPWM_CH5N/SPI_DO/SDA/P2.10_34") (pintype "passive+no_connect"))
    )
    (net (code "83") (name "unconnected-(U4-P0.15{slash}CMP2_OUT{slash}MCPWM_CH0P{slash}UART0_RXD{slash}SPI_DO{slash}SDA{slash}TIM0_CH0{slash}CMP0_IN-Pad12)") (class "Default")
      (node (ref "U4") (pin "12") (pinfunction "P0.15/CMP2_OUT/MCPWM_CH0P/UART0_RXD/SPI_DO/SDA/TIM0_CH0/CMP0_IN_12") (pintype "passive+no_connect"))
    )
    (net (code "84") (name "unconnected-(U4-P1.0{slash}MCPWM_CH0N{slash}UART0_TXD{slash}SPI_DI-Pad13)") (class "Default")
      (node (ref "U4") (pin "13") (pinfunction "P1.0/MCPWM_CH0N/UART0_TXD/SPI_DI_13") (pintype "passive+no_connect"))
    )
    (net (code "85") (name "unconnected-(U4-P3.5{slash}OPA0_IP-Pad14)") (class "Default")
      (node (ref "U4") (pin "14") (pinfunction "P3.5/OPA0_IP_14") (pintype "passive"))
    )
    (net (code "86") (name "unconnected-(U4-P3.7{slash}OPA0_IN-Pad15)") (class "Default")
      (node (ref "U4") (pin "15") (pinfunction "P3.7/OPA0_IN_15") (pintype "passive"))
    )
  )
)
